# 2_IsoCAN.net
KiCad netlist of a schematic drawn in Altium Designer
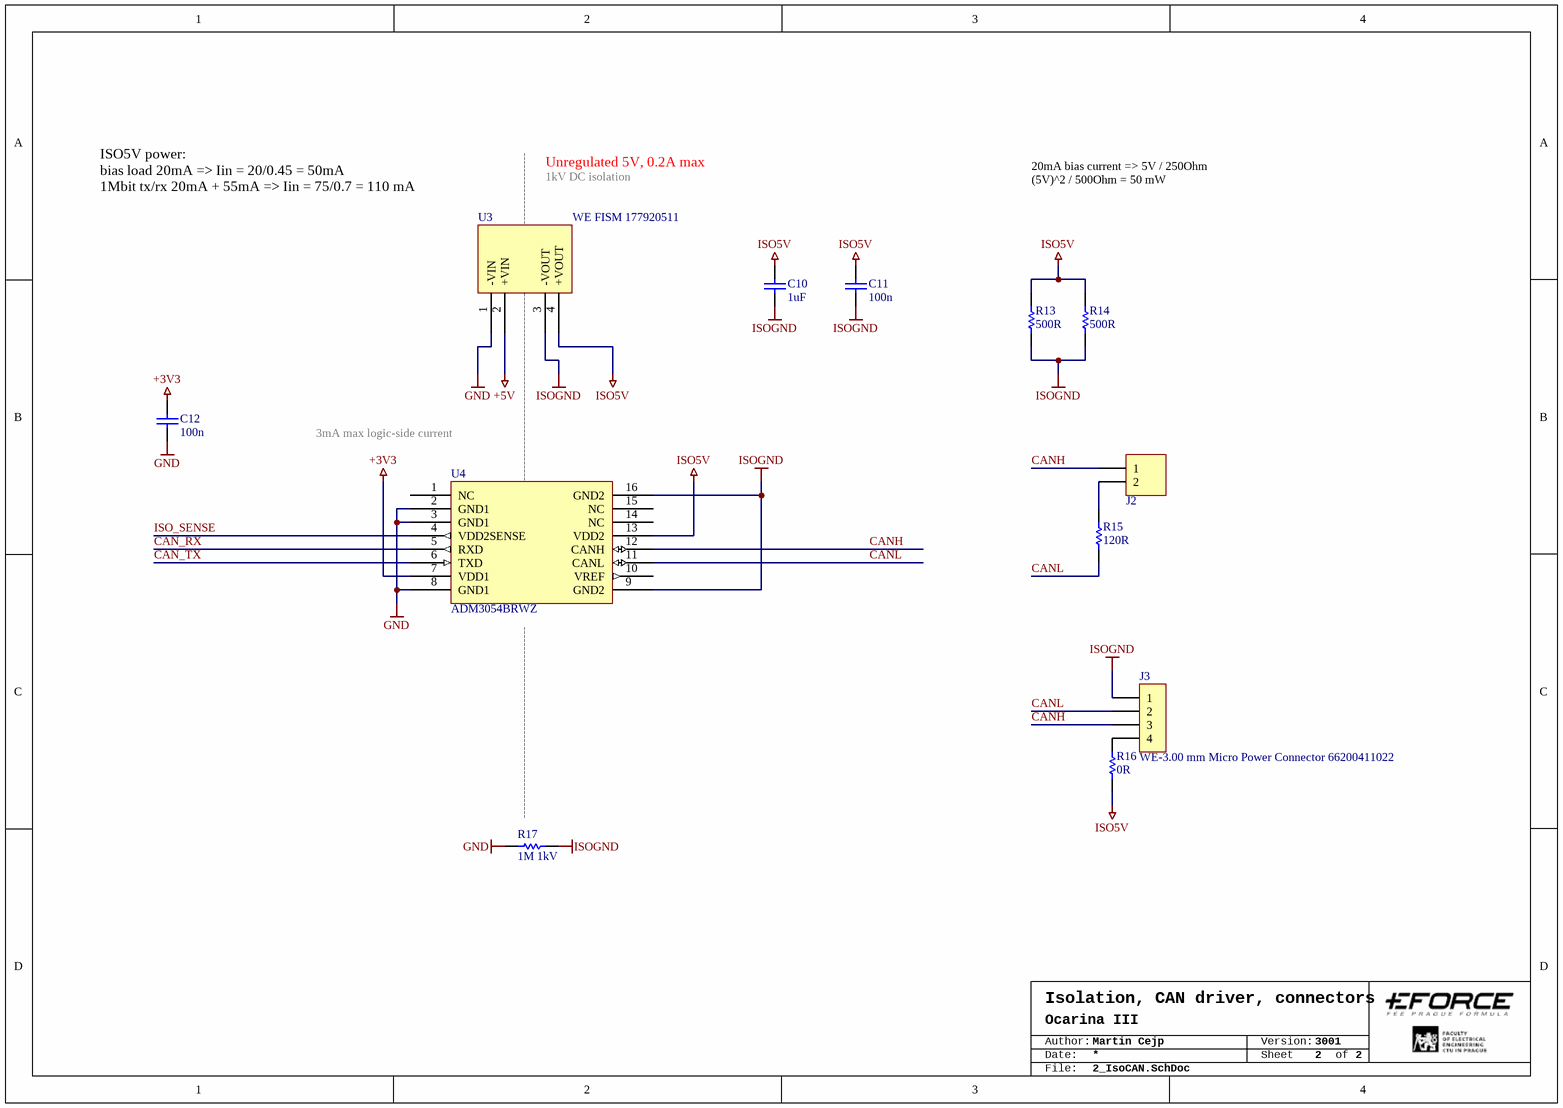
[diagram p0: 2_IsoCAN.SchDoc]

(export (version "E")
  (design (tool "Eeschema 10.0.6"))
  (components
    (comp (ref "C10")
      (value "1uF")
      (footprint "CAPC0805(2012)145_M")
      (description "CAP 1uF 16V ±20% 0805 (2012 Metric) Thickness 1.45mm SMD")
      (fields (field (name "TOLERANCE") "Â±20%"))
      (libsource (lib "Altium Content Vault") (part "CAP"))
    )
    (comp (ref "C11")
      (value "100n")
      (footprint "CAPC0603(1608)100_M")
      (description "CAP 100nF 6.3V ±10% 0603 (1608 Metric) Thickness 1mm SMD")
      (fields (field (name "TOLERANCE") "Â±10%"))
      (libsource (lib "Altium Content Vault") (part "CAP"))
    )
    (comp (ref "C12")
      (value "100n")
      (footprint "CAPC0603(1608)100_M")
      (description "CAP 100nF 6.3V ±10% 0603 (1608 Metric) Thickness 1mm SMD")
      (fields (field (name "TOLERANCE") "Â±10%"))
      (libsource (lib "Altium Content Vault") (part "CAP"))
    )
    (comp (ref "J2")
      (value "02p")
      (footprint "61300211121")
      (description "WR-PHD 2.54 mm THT Pin Header, 02p")
      (fields (field (name "PARTNUMBER") "61300211121") (field (name "PUBLISHER") "Wurth Elektronik"))
      (libsource (lib "ALTIUM-PHD_2_54_THT_PIN_HEADER_6130XX11121-rev16c") (part "61300211121"))
    )
    (comp (ref "J3")
      (value "WE-3.00 mm Micro Power Connector 66200411022")
      (footprint "66200411022")
      (description "WR-MPC3 3.00 mm Male Single Row Angled Header")
      (fields
        (field (name "MANUFACTURER") "W¨ąrth Elektronik eiSos GmbH")
        (field (name "PARTNO") "66200411022")
        (field (name "CREATED BY") "Karrer Zheng")
      )
      (libsource (lib "ALTIUM-WR-MPC3_MALE_HEADER-rev16b") (part "WE-3.00 mm Micro Power Connector 66200411022"))
    )
    (comp (ref "R13")
      (value "500R")
      (footprint "RESC0603(1608)_L")
      (description "120R 0.1W 5% 0603 (1608 Metric)  SMD")
      (fields (field (name "POWER") "0.1 W") (field (name "TOLERANCE") "5 %"))
      (libsource (lib "Altium Content Vault") (part "RES"))
    )
    (comp (ref "R14")
      (value "500R")
      (footprint "RESC0603(1608)_L")
      (description "120R 0.1W 5% 0603 (1608 Metric)  SMD")
      (fields (field (name "POWER") "0.1 W") (field (name "TOLERANCE") "5 %"))
      (libsource (lib "Altium Content Vault") (part "RES"))
    )
    (comp (ref "R15")
      (value "120R")
      (footprint "RESC0603(1608)_L")
      (description "120R 0.1W 5% 0603 (1608 Metric)  SMD")
      (fields (field (name "POWER") "0.1 W") (field (name "TOLERANCE") "5 %"))
      (libsource (lib "Altium Content Vault") (part "RES"))
    )
    (comp (ref "R16")
      (value "0R")
      (footprint "RESC0603(1608)_L")
      (description "0R 0.1W 5% 0603 (1608 Metric)  SMD")
      (fields (field (name "POWER") "0.1 W") (field (name "TOLERANCE") "5 %"))
      (libsource (lib "Altium Content Vault") (part "CMP-1012-00052-1"))
    )
    (comp (ref "R17")
      (value "1M 1kV")
      (footprint "RESC1206(3216)_L")
      (description "1M 0.25W 5% 1206 (3216 Metric)  SMD")
      (fields (field (name "POWER") "0.25 W") (field (name "TOLERANCE") "5 %"))
      (libsource (lib "Altium Content Vault") (part "RES"))
    )
    (comp (ref "U3")
      (value "WE FISM 177920511")
      (footprint "FISM_17792XXX1")
      (libsource (lib "WE_FISM_177920511") (part "177920511"))
    )
    (comp (ref "U4")
      (value "ADM3054BRWZ")
      (footprint "SOIC127P1030X265-16N")
      (libsource (lib "ADM3054BRWZ") (part "ADM3054BRWZ"))
    )
  )
  (nets
    (net (code "1") (name "+3V3") (class "Default")
      (node (ref "C12") (pin "2") (pinfunction "2_2") (pintype "passive"))
      (node (ref "U4") (pin "7") (pinfunction "VDD1_7") (pintype "power_in"))
    )
    (net (code "2") (name "+5V") (class "Default")
      (node (ref "U3") (pin "2") (pinfunction "+VIN_2") (pintype "power_in"))
    )
    (net (code "3") (name "/CANH") (class "Default")
      (node (ref "J2") (pin "1") (pinfunction "1_1") (pintype "passive"))
      (node (ref "J3") (pin "3") (pinfunction "3_3") (pintype "passive"))
      (node (ref "U4") (pin "12") (pinfunction "CANH_12") (pintype "bidirectional"))
    )
    (net (code "4") (name "/CANL") (class "Default")
      (node (ref "J3") (pin "2") (pinfunction "2_2") (pintype "passive"))
      (node (ref "R15") (pin "1") (pinfunction "1_1") (pintype "passive"))
      (node (ref "U4") (pin "11") (pinfunction "CANL_11") (pintype "bidirectional"))
    )
    (net (code "5") (name "/CAN_RX") (class "Default")
      (node (ref "U4") (pin "5") (pinfunction "RXD_5") (pintype "output"))
    )
    (net (code "6") (name "/CAN_TX") (class "Default")
      (node (ref "U4") (pin "6") (pinfunction "TXD_6") (pintype "input"))
    )
    (net (code "7") (name "/ISO_SENSE") (class "Default")
      (node (ref "U4") (pin "4") (pinfunction "VDD2SENSE_4") (pintype "output"))
    )
    (net (code "8") (name "GND") (class "Default")
      (node (ref "C12") (pin "1") (pinfunction "1_1") (pintype "passive"))
      (node (ref "R17") (pin "1") (pinfunction "1_1") (pintype "passive"))
      (node (ref "U3") (pin "1") (pinfunction "-VIN_1") (pintype "power_in"))
      (node (ref "U4") (pin "2") (pinfunction "GND1_2") (pintype "passive"))
      (node (ref "U4") (pin "3") (pinfunction "GND1_3") (pintype "passive"))
      (node (ref "U4") (pin "8") (pinfunction "GND1_8") (pintype "power_in"))
    )
    (net (code "9") (name "ISO5V") (class "Default")
      (node (ref "C10") (pin "2") (pinfunction "2_2") (pintype "passive"))
      (node (ref "C11") (pin "2") (pinfunction "2_2") (pintype "passive"))
      (node (ref "R13") (pin "2") (pinfunction "2_2") (pintype "passive"))
      (node (ref "R14") (pin "2") (pinfunction "2_2") (pintype "passive"))
      (node (ref "R16") (pin "1") (pinfunction "1_1") (pintype "passive"))
      (node (ref "U3") (pin "4") (pinfunction "+VOUT_4") (pintype "power_in"))
      (node (ref "U4") (pin "13") (pinfunction "VDD2_13") (pintype "power_in"))
    )
    (net (code "10") (name "ISOGND") (class "Default")
      (node (ref "C10") (pin "1") (pinfunction "1_1") (pintype "passive"))
      (node (ref "C11") (pin "1") (pinfunction "1_1") (pintype "passive"))
      (node (ref "J3") (pin "1") (pinfunction "1_1") (pintype "passive"))
      (node (ref "R13") (pin "1") (pinfunction "1_1") (pintype "passive"))
      (node (ref "R14") (pin "1") (pinfunction "1_1") (pintype "passive"))
      (node (ref "R17") (pin "2") (pinfunction "2_2") (pintype "passive"))
      (node (ref "U3") (pin "3") (pinfunction "-VOUT_3") (pintype "power_in"))
      (node (ref "U4") (pin "16") (pinfunction "GND2_16") (pintype "power_in"))
      (node (ref "U4") (pin "9") (pinfunction "GND2_9") (pintype "power_in"))
    )
    (net (code "11") (name "Net-(J2-Pad2)") (class "Default")
      (node (ref "J2") (pin "2") (pinfunction "2_2") (pintype "passive"))
      (node (ref "R15") (pin "2") (pinfunction "2_2") (pintype "passive"))
    )
    (net (code "12") (name "Net-(J3-Pad4)") (class "Default")
      (node (ref "J3") (pin "4") (pinfunction "4_4") (pintype "passive"))
      (node (ref "R16") (pin "2") (pinfunction "2_2") (pintype "passive"))
    )
    (net (code "13") (name "unconnected-(U4-NC-Pad1)") (class "Default")
      (node (ref "U4") (pin "1") (pinfunction "NC_1") (pintype "passive"))
    )
    (net (code "14") (name "unconnected-(U4-NC-Pad14)") (class "Default")
      (node (ref "U4") (pin "14") (pinfunction "NC_14") (pintype "passive"))
    )
    (net (code "15") (name "unconnected-(U4-NC-Pad15)") (class "Default")
      (node (ref "U4") (pin "15") (pinfunction "NC_15") (pintype "passive"))
    )
    (net (code "16") (name "unconnected-(U4-VREF-Pad10)") (class "Default")
      (node (ref "U4") (pin "10") (pinfunction "VREF_10") (pintype "output"))
    )
  )
)
